# ProDoc_ChisFlash-MBCX-CQZ_2025-11-29.net
KiCad netlist of a schematic drawn in EasyEDA Pro
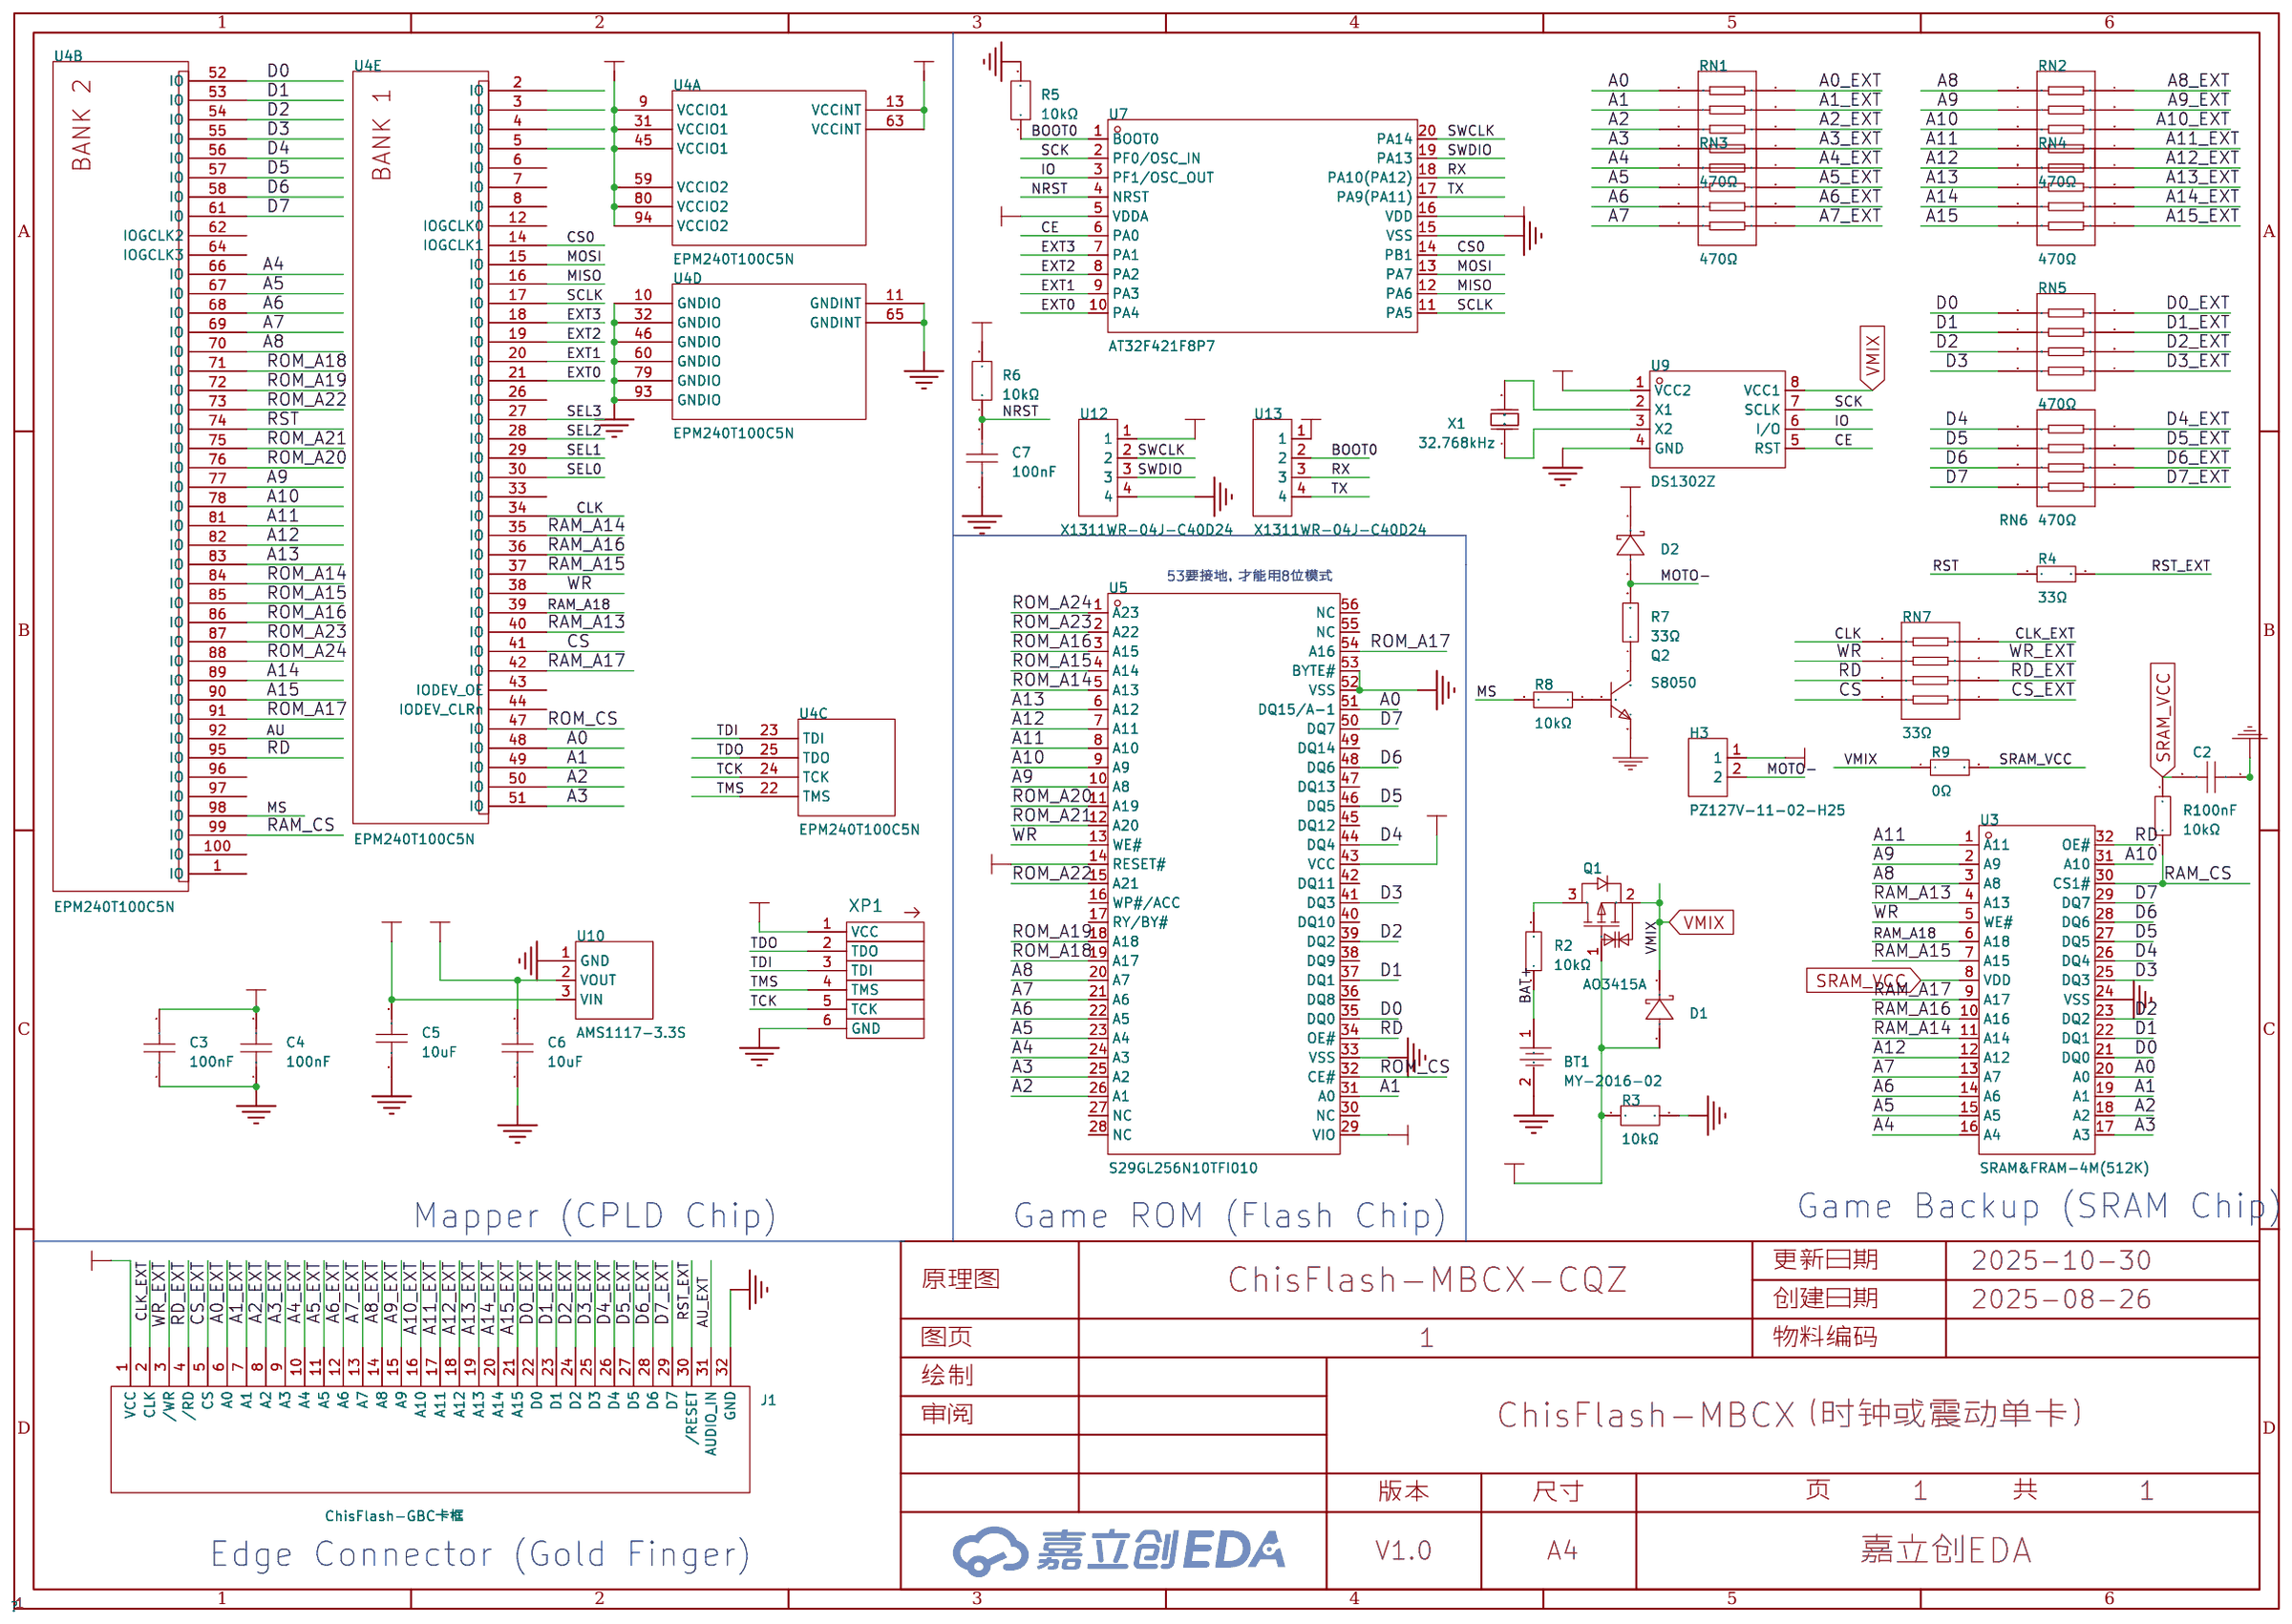
[diagram p0: schematic sheet]

(export (version "E")
  (design (tool "Eeschema 10.0.6"))
  (components
    (comp (ref "BT1")
      (value "MY-2016-02")
      (footprint "easyedapro:BAT-SMD_MY-2032-08")
      (description "连接器类型:电池扣;适用电池规格:CR2016;触头材质:磷青铜;触点电镀:镍;工作温度范围:-25°C~+85°C;")
      (fields (field (name "Manufacturer") "MYOUNG(美阳)"))
      (libsource (lib "easyedapro") (part "MY-2016-02"))
    )
    (comp (ref "C2")
      (value "100nF")
      (footprint "easyedapro:C0603")
      (description "容值:100nF;精度:±10%;额定电压:50V;材质(温度系数):X7R;")
      (fields
        (field (name "Manufacturer Part") "CGA0603X7R104K500JT")
        (field (name "Manufacturer") "HRE(芯声)")
      )
      (libsource (lib "easyedapro") (part "CGA0603X7R104K500JT"))
    )
    (comp (ref "C3")
      (value "100nF")
      (footprint "easyedapro:C0603")
      (description "容值:100nF;精度:±10%;额定电压:50V;材质(温度系数):X7R;")
      (fields
        (field (name "Manufacturer Part") "CGA0603X7R104K500JT")
        (field (name "Manufacturer") "HRE(芯声)")
      )
      (libsource (lib "easyedapro") (part "CGA0603X7R104K500JT"))
    )
    (comp (ref "C4")
      (value "100nF")
      (footprint "easyedapro:C0603")
      (description "容值:100nF;精度:±10%;额定电压:50V;材质(温度系数):X7R;")
      (fields
        (field (name "Manufacturer Part") "CGA0603X7R104K500JT")
        (field (name "Manufacturer") "HRE(芯声)")
      )
      (libsource (lib "easyedapro") (part "CGA0603X7R104K500JT"))
    )
    (comp (ref "C5")
      (value "10uF")
      (footprint "easyedapro:C0603")
      (description "容值:10uF;精度:±20%;额定电压:25V;材质(温度系数):X5R;")
      (fields
        (field (name "Manufacturer Part") "CL10A106MA8NRNC")
        (field (name "Manufacturer") "SAMSUNG(三星)")
      )
      (libsource (lib "easyedapro") (part "CL10A106MA8NRNC"))
    )
    (comp (ref "C6")
      (value "10uF")
      (footprint "easyedapro:C0603")
      (description "容值:10uF;精度:±20%;额定电压:25V;材质(温度系数):X5R;")
      (fields
        (field (name "Manufacturer Part") "CL10A106MA8NRNC")
        (field (name "Manufacturer") "SAMSUNG(三星)")
      )
      (libsource (lib "easyedapro") (part "CL10A106MA8NRNC"))
    )
    (comp (ref "C7")
      (value "100nF")
      (footprint "easyedapro:C0603")
      (description "容值:100nF;精度:±10%;额定电压:50V;材质(温度系数):X7R;")
      (fields
        (field (name "Manufacturer Part") "CGA0603X7R104K500JT")
        (field (name "Manufacturer") "HRE(芯声)")
      )
      (libsource (lib "easyedapro") (part "CGA0603X7R104K500JT"))
    )
    (comp (ref "D1")
      (value "RB751V-40")
      (footprint "easyedapro:SOD-323_L1.7-W1.3-LS2.6-RD-1")
      (description "二极管配置:独立式;正向压降(Vf):370mV@1mA;直流反向耐压(Vr):40V;平均整流电流(Io):30mA;")
      (fields (field (name "Manufacturer") "宏迦橙"))
      (libsource (lib "easyedapro") (part "RB751V-40_C7502691"))
    )
    (comp (ref "D2")
      (value "RB751V-40")
      (footprint "easyedapro:SOD-323_L1.7-W1.3-LS2.6-RD-1")
      (description "二极管配置:独立式;正向压降(Vf):370mV@1mA;直流反向耐压(Vr):40V;平均整流电流(Io):30mA;")
      (fields (field (name "Manufacturer") "宏迦橙"))
      (libsource (lib "easyedapro") (part "RB751V-40_C7502691"))
    )
    (comp (ref "H3")
      (value "PZ127V-11-02-H25")
      (footprint "easyedapro:HDR-TH_2P-P1.27-V-M-1")
      (fields (field (name "Manufacturer") "XFCN(兴飞)"))
      (libsource (lib "easyedapro") (part "PZ127V-11-02-H25"))
    )
    (comp (ref "J1")
      (value "ChisFlash-GBC卡框")
      (footprint "easyedapro:ChisFlash-GBC卡框")
      (libsource (lib "easyedapro") (part "ChisFlash-GBC卡框"))
    )
    (comp (ref "Q1")
      (value "AO3415A")
      (footprint "easyedapro:SOT-23-3_L3.0-W1.7-P0.95-LS2.9-BR")
      (fields (field (name "Manufacturer") "UMW(友台半导体)"))
      (libsource (lib "easyedapro") (part "AO3415A_C347479"))
    )
    (comp (ref "Q2")
      (value "S8050")
      (footprint "easyedapro:SOT-23-3_L2.9-W1.3-P1.90-LS2.3-BR")
      (description "晶体管类型:NPN;集电极电流(Ic):500mA;集射极击穿电压(Vceo):25V;耗散功率(Pd):300mW;直流电流增益(hFE):120@50mA,1.0V;")
      (fields (field (name "Manufacturer") "宏嘉诚"))
      (libsource (lib "easyedapro") (part "S8050_C20069125"))
    )
    (comp (ref "R1")
      (value "10kΩ")
      (footprint "easyedapro:R0603")
      (description "电阻类型:厚膜电阻;阻值:10kΩ;精度:±1%;功率:100mW;温度系数:±100ppm/°C;最大工作电压:75V;工作温度范围:-55°C~+155°C;")
      (fields
        (field (name "Manufacturer Part") "0603WAF1002T5E")
        (field (name "Manufacturer") "UNI-ROYAL(厚声)")
      )
      (libsource (lib "easyedapro") (part "0603WAF1002T5E"))
    )
    (comp (ref "R2")
      (value "10kΩ")
      (footprint "easyedapro:R0603")
      (description "电阻类型:厚膜电阻;阻值:10kΩ;精度:±1%;功率:100mW;温度系数:±100ppm/°C;最大工作电压:75V;工作温度范围:-55°C~+155°C;")
      (fields
        (field (name "Manufacturer Part") "0603WAF1002T5E")
        (field (name "Manufacturer") "UNI-ROYAL(厚声)")
      )
      (libsource (lib "easyedapro") (part "0603WAF1002T5E"))
    )
    (comp (ref "R3")
      (value "10kΩ")
      (footprint "easyedapro:R0603")
      (description "电阻类型:薄膜电阻;阻值:10kΩ;精度:±0.1%;功率:100mW;最大工作电压:75V;温度系数:±25ppm/°C;")
      (fields (field (name "Manufacturer Part") "RT0603BRD1010KL") (field (name "Manufacturer") "YAGEO(国巨)"))
      (libsource (lib "easyedapro") (part "RT0603BRD1010KL"))
    )
    (comp (ref "R4")
      (value "33Ω")
      (footprint "easyedapro:R0603")
      (description "电阻类型:厚膜电阻;阻值:33Ω;精度:±1%;功率:100mW;最大工作电压:75V;温度系数:±100ppm/°C;")
      (fields
        (field (name "Manufacturer Part") "0603WAF330JT5E")
        (field (name "Manufacturer") "UNI-ROYAL(厚声)")
      )
      (libsource (lib "easyedapro") (part "0603WAF330JT5E"))
    )
    (comp (ref "R5")
      (value "10kΩ")
      (footprint "easyedapro:R0603")
      (description "电阻类型:薄膜电阻;阻值:10kΩ;精度:±0.1%;功率:100mW;最大工作电压:75V;温度系数:±25ppm/°C;")
      (fields (field (name "Manufacturer Part") "RT0603BRD1010KL") (field (name "Manufacturer") "YAGEO(国巨)"))
      (libsource (lib "easyedapro") (part "RT0603BRD1010KL"))
    )
    (comp (ref "R6")
      (value "10kΩ")
      (footprint "easyedapro:R0603")
      (description "电阻类型:薄膜电阻;阻值:10kΩ;精度:±0.1%;功率:100mW;最大工作电压:75V;温度系数:±25ppm/°C;")
      (fields (field (name "Manufacturer Part") "RT0603BRD1010KL") (field (name "Manufacturer") "YAGEO(国巨)"))
      (libsource (lib "easyedapro") (part "RT0603BRD1010KL"))
    )
    (comp (ref "R7")
      (value "33Ω")
      (footprint "easyedapro:R0603")
      (description "电阻类型:厚膜电阻;阻值:33Ω;精度:±1%;功率:100mW;最大工作电压:75V;温度系数:±100ppm/°C;")
      (fields
        (field (name "Manufacturer Part") "0603WAF330JT5E")
        (field (name "Manufacturer") "UNI-ROYAL(厚声)")
      )
      (libsource (lib "easyedapro") (part "0603WAF330JT5E"))
    )
    (comp (ref "R8")
      (value "10kΩ")
      (footprint "easyedapro:R0603")
      (description "电阻类型:厚膜电阻;阻值:10kΩ;精度:±1%;功率:100mW;温度系数:±100ppm/°C;最大工作电压:75V;工作温度范围:-55°C~+155°C;")
      (fields
        (field (name "Manufacturer Part") "0603WAF1002T5E")
        (field (name "Manufacturer") "UNI-ROYAL(厚声)")
      )
      (libsource (lib "easyedapro") (part "0603WAF1002T5E"))
    )
    (comp (ref "R9")
      (value "0Ω")
      (footprint "easyedapro:R0603")
      (description "电阻类型:厚膜电阻;阻值:0Ω;精度:±1%;功率:100mW;工作电压:75V;温度系数:-;")
      (fields
        (field (name "Manufacturer Part") "0603WAF0000T5E")
        (field (name "Manufacturer") "UNI-ROYAL(厚声)")
      )
      (libsource (lib "easyedapro") (part "0603WAF0000T5E"))
    )
    (comp (ref "RN1")
      (value "470Ω")
      (footprint "easyedapro:RES-ARRAY-SMD_0603-8P-L3.2-W1.6-BL")
      (description "电阻器数:4;阻值:470Ω;精度:±5%;单个元件功率:62.5mW;温度系数:±200ppm/°C;")
      (fields
        (field (name "Manufacturer Part") "4D03WGJ0471T5E")
        (field (name "Manufacturer") "UNI-ROYAL(厚声)")
      )
      (libsource (lib "easyedapro") (part "4D03WGJ0471T5E"))
    )
    (comp (ref "RN2")
      (value "470Ω")
      (footprint "easyedapro:RES-ARRAY-SMD_0603-8P-L3.2-W1.6-BL")
      (description "电阻器数:4;阻值:470Ω;精度:±5%;单个元件功率:62.5mW;温度系数:±200ppm/°C;")
      (fields
        (field (name "Manufacturer Part") "4D03WGJ0471T5E")
        (field (name "Manufacturer") "UNI-ROYAL(厚声)")
      )
      (libsource (lib "easyedapro") (part "4D03WGJ0471T5E"))
    )
    (comp (ref "RN3")
      (value "470Ω")
      (footprint "easyedapro:RES-ARRAY-SMD_0603-8P-L3.2-W1.6-BL")
      (description "电阻器数:4;阻值:470Ω;精度:±5%;单个元件功率:62.5mW;温度系数:±200ppm/°C;")
      (fields
        (field (name "Manufacturer Part") "4D03WGJ0471T5E")
        (field (name "Manufacturer") "UNI-ROYAL(厚声)")
      )
      (libsource (lib "easyedapro") (part "4D03WGJ0471T5E"))
    )
    (comp (ref "RN4")
      (value "470Ω")
      (footprint "easyedapro:RES-ARRAY-SMD_0603-8P-L3.2-W1.6-BL")
      (description "电阻器数:4;阻值:470Ω;精度:±5%;单个元件功率:62.5mW;温度系数:±200ppm/°C;")
      (fields
        (field (name "Manufacturer Part") "4D03WGJ0471T5E")
        (field (name "Manufacturer") "UNI-ROYAL(厚声)")
      )
      (libsource (lib "easyedapro") (part "4D03WGJ0471T5E"))
    )
    (comp (ref "RN5")
      (value "470Ω")
      (footprint "easyedapro:RES-ARRAY-SMD_0603-8P-L3.2-W1.6-BL")
      (description "电阻器数:4;阻值:470Ω;精度:±5%;单个元件功率:62.5mW;温度系数:±200ppm/°C;")
      (fields
        (field (name "Manufacturer Part") "4D03WGJ0471T5E")
        (field (name "Manufacturer") "UNI-ROYAL(厚声)")
      )
      (libsource (lib "easyedapro") (part "4D03WGJ0471T5E"))
    )
    (comp (ref "RN6")
      (value "470Ω")
      (footprint "easyedapro:RES-ARRAY-SMD_0603-8P-L3.2-W1.6-BL")
      (description "电阻器数:4;阻值:470Ω;精度:±5%;单个元件功率:62.5mW;温度系数:±200ppm/°C;")
      (fields
        (field (name "Manufacturer Part") "4D03WGJ0471T5E")
        (field (name "Manufacturer") "UNI-ROYAL(厚声)")
      )
      (libsource (lib "easyedapro") (part "4D03WGJ0471T5E"))
    )
    (comp (ref "RN7")
      (value "33Ω")
      (footprint "easyedapro:RES-ARRAY-SMD_0603-8P-L3.2-W1.6-BL")
      (description "电阻器数:4;阻值:470Ω;精度:±5%;单个元件功率:62.5mW;温度系数:±200ppm/°C;")
      (fields
        (field (name "Manufacturer Part") "4D03WGF330JT5E")
        (field (name "Manufacturer") "UNI-ROYAL(厚声)")
      )
      (libsource (lib "easyedapro") (part "4D03WGJ0471T5E"))
    )
    (comp (ref "U3")
      (value "SRAM&FRAM-4M(512K)")
      (footprint "easyedapro:TSSOP-TSOP二合一_1")
      (libsource (lib "easyedapro") (part "SRAM&FRAM-4M(512K)"))
    )
    (comp (ref "U4")
      (value "EPM240T100C5N")
      (footprint "easyedapro:TQFP-100_L14.0-W14.0-P0.50-LS16.0-BL")
      (description "类型:其它PLD;逻辑门数量:-;逻辑单元数:-;逻辑阵列块数:240;")
      (fields (field (name "Manufacturer") "Intel/Altera"))
      (libsource (lib "easyedapro") (part "EPM240T100C5N"))
    )
    (comp (ref "U5")
      (value "S29GL256N10TFI010")
      (footprint "easyedapro:TSOP-56_L18.4-W14.0-P0.50-LS20.0-TL")
      (libsource (lib "easyedapro") (part "S29GL256N10TFI010"))
    )
    (comp (ref "U7")
      (value "AT32F421F8P7")
      (footprint "easyedapro:TSSOP-20_L6.5-W4.4-P0.65-LS6.4-BL")
      (fields (field (name "Manufacturer") "ARTERY(雅特力)"))
      (libsource (lib "easyedapro") (part "AT32F421F8P7"))
    )
    (comp (ref "U9")
      (value "DS1302Z")
      (footprint "easyedapro:SOP-8_L4.9-W3.9-P1.27-LS6.0-BL-1")
      (description "接口:三线串行接口;")
      (fields (field (name "Manufacturer") "JSMSEMI(杰盛微)"))
      (libsource (lib "easyedapro") (part "DS1302Z"))
    )
    (comp (ref "U10")
      (value "AMS1117-3.3S")
      (footprint "easyedapro:SOT-89-3_L4.5-W2.5-P1.50-LS4.2-BR")
      (description "输出类型:固定;工作电压:18V;输出电压:3.3V;输出电流:1A;电源纹波抑制比(PSRR):60dB@(120Hz);输出极性:正极;")
      (fields (field (name "Manufacturer") "UMW(友台半导体)"))
      (libsource (lib "easyedapro") (part "AMS1117-3.3_C347256"))
    )
    (comp (ref "U12")
      (value "X1311WR-04J-C40D24")
      (footprint "easyedapro:HDR-TH_4P-P1.27-H-M-W7.0-N_1")
      (fields (field (name "Manufacturer") "XKB Connection(中国星坤)"))
      (libsource (lib "easyedapro") (part "X1311WR-04J-C40D24"))
    )
    (comp (ref "U13")
      (value "X1311WR-04J-C40D24")
      (footprint "easyedapro:HDR-TH_4P-P1.27-H-M-W7.0-N_1")
      (fields (field (name "Manufacturer") "XKB Connection(中国星坤)"))
      (libsource (lib "easyedapro") (part "X1311WR-04J-C40D24"))
    )
    (comp (ref "X1")
      (value "32.768kHz")
      (footprint "easyedapro:CRYSTAL-SMD_2P-L2.0-W1.2")
      (description "晶振类型:贴片晶振;频率:32.768kHz;常温频差:±20ppm;负载电容:12.5pF;频率稳定度:±30ppm;")
      (fields
        (field (name "Manufacturer Part") "XKHEL89CGI-112YLC-32.768K")
        (field (name "Manufacturer") "YXC(扬兴晶振)")
      )
      (libsource (lib "easyedapro") (part "XKHEL89CGI-112YLC-32.768K"))
    )
    (comp (ref "XP1")
      (value "JTAG")
      (footprint "easyedapro:HDR-TH_6P-P1.27-V-M-1")
      (libsource (lib "easyedapro") (part "jtag"))
    )
  )
  (nets
    (net (code "1") (name "+3V3") (class "Default")
      (node (ref "C3") (pin "2") (pinfunction "2_2") (pintype "unspecified"))
      (node (ref "C4") (pin "2") (pinfunction "2_2") (pintype "unspecified"))
      (node (ref "C6") (pin "2") (pinfunction "2_2") (pintype "unspecified"))
      (node (ref "D1") (pin "2") (pinfunction "A_2") (pintype "unspecified"))
      (node (ref "D2") (pin "1") (pinfunction "K_1") (pintype "unspecified"))
      (node (ref "H3") (pin "1") (pinfunction "1_1") (pintype "unspecified"))
      (node (ref "Q1") (pin "1") (pinfunction "G_1") (pintype "unspecified"))
      (node (ref "R3") (pin "1") (pinfunction "1_1") (pintype "unspecified"))
      (node (ref "R6") (pin "2") (pinfunction "2_2") (pintype "unspecified"))
      (node (ref "U10") (pin "2") (pinfunction "VOUT_2") (pintype "unspecified"))
      (node (ref "U12") (pin "1") (pinfunction "1_1") (pintype "unspecified"))
      (node (ref "U13") (pin "1") (pinfunction "1_1") (pintype "unspecified"))
      (node (ref "U4") (pin "13") (pinfunction "VCCINT_13") (pintype "unspecified"))
      (node (ref "U4") (pin "31") (pinfunction "VCCIO1_31") (pintype "unspecified"))
      (node (ref "U4") (pin "45") (pinfunction "VCCIO1_45") (pintype "unspecified"))
      (node (ref "U4") (pin "59") (pinfunction "VCCIO2_59") (pintype "unspecified"))
      (node (ref "U4") (pin "63") (pinfunction "VCCINT_63") (pintype "unspecified"))
      (node (ref "U4") (pin "80") (pinfunction "VCCIO2_80") (pintype "unspecified"))
      (node (ref "U4") (pin "9") (pinfunction "VCCIO1_9") (pintype "unspecified"))
      (node (ref "U4") (pin "94") (pinfunction "VCCIO2_94") (pintype "unspecified"))
      (node (ref "U5") (pin "14") (pinfunction "RESET#_14") (pintype "unspecified"))
      (node (ref "U5") (pin "29") (pinfunction "VIO_29") (pintype "unspecified"))
      (node (ref "U5") (pin "43") (pinfunction "VCC_43") (pintype "unspecified"))
      (node (ref "U7") (pin "16") (pinfunction "VDD_16") (pintype "unspecified"))
      (node (ref "U7") (pin "5") (pinfunction "VDDA_5") (pintype "unspecified"))
      (node (ref "U9") (pin "1") (pinfunction "VCC2_1") (pintype "unspecified"))
      (node (ref "XP1") (pin "1") (pinfunction "VCC_1") (pintype "output"))
    )
    (net (code "2") (name "+5V") (class "Default")
      (node (ref "C5") (pin "2") (pinfunction "2_2") (pintype "unspecified"))
      (node (ref "J1") (pin "1") (pinfunction "VCC_1") (pintype "unspecified"))
      (node (ref "U10") (pin "3") (pinfunction "VIN_3") (pintype "unspecified"))
    )
    (net (code "3") (name "/A0") (class "Default")
      (node (ref "RN1") (pin "8") (pinfunction "8_8") (pintype "input"))
      (node (ref "U3") (pin "20") (pinfunction "A0_20") (pintype "unspecified"))
      (node (ref "U4") (pin "48") (pinfunction "IO_48") (pintype "bidirectional"))
      (node (ref "U5") (pin "51") (pinfunction "DQ15/A-1_51") (pintype "unspecified"))
    )
    (net (code "4") (name "/A0_EXT") (class "Default")
      (node (ref "J1") (pin "6") (pinfunction "A0_6") (pintype "unspecified"))
      (node (ref "RN1") (pin "1") (pinfunction "1_1") (pintype "input"))
    )
    (net (code "5") (name "/A1") (class "Default")
      (node (ref "RN1") (pin "7") (pinfunction "7_7") (pintype "input"))
      (node (ref "U3") (pin "19") (pinfunction "A1_19") (pintype "unspecified"))
      (node (ref "U4") (pin "49") (pinfunction "IO_49") (pintype "bidirectional"))
      (node (ref "U5") (pin "31") (pinfunction "A0_31") (pintype "unspecified"))
    )
    (net (code "6") (name "/A1_EXT") (class "Default")
      (node (ref "J1") (pin "7") (pinfunction "A1_7") (pintype "unspecified"))
      (node (ref "RN1") (pin "2") (pinfunction "2_2") (pintype "input"))
    )
    (net (code "7") (name "/A2") (class "Default")
      (node (ref "RN1") (pin "6") (pinfunction "6_6") (pintype "input"))
      (node (ref "U3") (pin "18") (pinfunction "A2_18") (pintype "unspecified"))
      (node (ref "U4") (pin "50") (pinfunction "IO_50") (pintype "bidirectional"))
      (node (ref "U5") (pin "26") (pinfunction "A1_26") (pintype "unspecified"))
    )
    (net (code "8") (name "/A2_EXT") (class "Default")
      (node (ref "J1") (pin "8") (pinfunction "A2_8") (pintype "unspecified"))
      (node (ref "RN1") (pin "3") (pinfunction "3_3") (pintype "input"))
    )
    (net (code "9") (name "/A3") (class "Default")
      (node (ref "RN1") (pin "5") (pinfunction "5_5") (pintype "input"))
      (node (ref "U3") (pin "17") (pinfunction "A3_17") (pintype "unspecified"))
      (node (ref "U4") (pin "51") (pinfunction "IO_51") (pintype "bidirectional"))
      (node (ref "U5") (pin "25") (pinfunction "A2_25") (pintype "unspecified"))
    )
    (net (code "10") (name "/A3_EXT") (class "Default")
      (node (ref "J1") (pin "9") (pinfunction "A3_9") (pintype "unspecified"))
      (node (ref "RN1") (pin "4") (pinfunction "4_4") (pintype "input"))
    )
    (net (code "11") (name "/A4") (class "Default")
      (node (ref "RN3") (pin "8") (pinfunction "8_8") (pintype "input"))
      (node (ref "U3") (pin "16") (pinfunction "A4_16") (pintype "unspecified"))
      (node (ref "U4") (pin "66") (pinfunction "IO_66") (pintype "bidirectional"))
      (node (ref "U5") (pin "24") (pinfunction "A3_24") (pintype "unspecified"))
    )
    (net (code "12") (name "/A4_EXT") (class "Default")
      (node (ref "J1") (pin "10") (pinfunction "A4_10") (pintype "unspecified"))
      (node (ref "RN3") (pin "1") (pinfunction "1_1") (pintype "input"))
    )
    (net (code "13") (name "/A5") (class "Default")
      (node (ref "RN3") (pin "7") (pinfunction "7_7") (pintype "input"))
      (node (ref "U3") (pin "15") (pinfunction "A5_15") (pintype "unspecified"))
      (node (ref "U4") (pin "67") (pinfunction "IO_67") (pintype "bidirectional"))
      (node (ref "U5") (pin "23") (pinfunction "A4_23") (pintype "unspecified"))
    )
    (net (code "14") (name "/A5_EXT") (class "Default")
      (node (ref "J1") (pin "11") (pinfunction "A5_11") (pintype "unspecified"))
      (node (ref "RN3") (pin "2") (pinfunction "2_2") (pintype "input"))
    )
    (net (code "15") (name "/A6") (class "Default")
      (node (ref "RN3") (pin "6") (pinfunction "6_6") (pintype "input"))
      (node (ref "U3") (pin "14") (pinfunction "A6_14") (pintype "unspecified"))
      (node (ref "U4") (pin "68") (pinfunction "IO_68") (pintype "bidirectional"))
      (node (ref "U5") (pin "22") (pinfunction "A5_22") (pintype "unspecified"))
    )
    (net (code "16") (name "/A6_EXT") (class "Default")
      (node (ref "J1") (pin "12") (pinfunction "A6_12") (pintype "unspecified"))
      (node (ref "RN3") (pin "3") (pinfunction "3_3") (pintype "input"))
    )
    (net (code "17") (name "/A7") (class "Default")
      (node (ref "RN3") (pin "5") (pinfunction "5_5") (pintype "input"))
      (node (ref "U3") (pin "13") (pinfunction "A7_13") (pintype "unspecified"))
      (node (ref "U4") (pin "69") (pinfunction "IO_69") (pintype "bidirectional"))
      (node (ref "U5") (pin "21") (pinfunction "A6_21") (pintype "unspecified"))
    )
    (net (code "18") (name "/A7_EXT") (class "Default")
      (node (ref "J1") (pin "13") (pinfunction "A7_13") (pintype "unspecified"))
      (node (ref "RN3") (pin "4") (pinfunction "4_4") (pintype "input"))
    )
    (net (code "19") (name "/A8") (class "Default")
      (node (ref "RN2") (pin "8") (pinfunction "8_8") (pintype "input"))
      (node (ref "U3") (pin "3") (pinfunction "A8_3") (pintype "unspecified"))
      (node (ref "U4") (pin "70") (pinfunction "IO_70") (pintype "bidirectional"))
      (node (ref "U5") (pin "20") (pinfunction "A7_20") (pintype "unspecified"))
    )
    (net (code "20") (name "/A8_EXT") (class "Default")
      (node (ref "J1") (pin "14") (pinfunction "A8_14") (pintype "unspecified"))
      (node (ref "RN2") (pin "1") (pinfunction "1_1") (pintype "input"))
    )
    (net (code "21") (name "/A9") (class "Default")
      (node (ref "RN2") (pin "7") (pinfunction "7_7") (pintype "input"))
      (node (ref "U3") (pin "2") (pinfunction "A9_2") (pintype "unspecified"))
      (node (ref "U4") (pin "77") (pinfunction "IO_77") (pintype "bidirectional"))
      (node (ref "U5") (pin "10") (pinfunction "A8_10") (pintype "unspecified"))
    )
    (net (code "22") (name "/A9_EXT") (class "Default")
      (node (ref "J1") (pin "15") (pinfunction "A9_15") (pintype "unspecified"))
      (node (ref "RN2") (pin "2") (pinfunction "2_2") (pintype "input"))
    )
    (net (code "23") (name "/A10") (class "Default")
      (node (ref "RN2") (pin "6") (pinfunction "6_6") (pintype "input"))
      (node (ref "U3") (pin "31") (pinfunction "A10_31") (pintype "unspecified"))
      (node (ref "U4") (pin "78") (pinfunction "IO_78") (pintype "bidirectional"))
      (node (ref "U5") (pin "9") (pinfunction "A9_9") (pintype "unspecified"))
    )
    (net (code "24") (name "/A10_EXT") (class "Default")
      (node (ref "J1") (pin "16") (pinfunction "A10_16") (pintype "unspecified"))
      (node (ref "RN2") (pin "3") (pinfunction "3_3") (pintype "input"))
    )
    (net (code "25") (name "/A11") (class "Default")
      (node (ref "RN2") (pin "5") (pinfunction "5_5") (pintype "input"))
      (node (ref "U3") (pin "1") (pinfunction "A11_1") (pintype "unspecified"))
      (node (ref "U4") (pin "81") (pinfunction "IO_81") (pintype "bidirectional"))
      (node (ref "U5") (pin "8") (pinfunction "A10_8") (pintype "unspecified"))
    )
    (net (code "26") (name "/A11_EXT") (class "Default")
      (node (ref "J1") (pin "17") (pinfunction "A11_17") (pintype "unspecified"))
      (node (ref "RN2") (pin "4") (pinfunction "4_4") (pintype "input"))
    )
    (net (code "27") (name "/A12") (class "Default")
      (node (ref "RN4") (pin "8") (pinfunction "8_8") (pintype "input"))
      (node (ref "U3") (pin "12") (pinfunction "A12_12") (pintype "unspecified"))
      (node (ref "U4") (pin "82") (pinfunction "IO_82") (pintype "bidirectional"))
      (node (ref "U5") (pin "7") (pinfunction "A11_7") (pintype "unspecified"))
    )
    (net (code "28") (name "/A12_EXT") (class "Default")
      (node (ref "J1") (pin "18") (pinfunction "A12_18") (pintype "unspecified"))
      (node (ref "RN4") (pin "1") (pinfunction "1_1") (pintype "input"))
    )
    (net (code "29") (name "/A13") (class "Default")
      (node (ref "RN4") (pin "7") (pinfunction "7_7") (pintype "input"))
      (node (ref "U4") (pin "83") (pinfunction "IO_83") (pintype "bidirectional"))
      (node (ref "U5") (pin "6") (pinfunction "A12_6") (pintype "unspecified"))
    )
    (net (code "30") (name "/A13_EXT") (class "Default")
      (node (ref "J1") (pin "19") (pinfunction "A13_19") (pintype "unspecified"))
      (node (ref "RN4") (pin "2") (pinfunction "2_2") (pintype "input"))
    )
    (net (code "31") (name "/A14") (class "Default")
      (node (ref "RN4") (pin "6") (pinfunction "6_6") (pintype "input"))
      (node (ref "U4") (pin "89") (pinfunction "IO_89") (pintype "bidirectional"))
    )
    (net (code "32") (name "/A14_EXT") (class "Default")
      (node (ref "J1") (pin "20") (pinfunction "A14_20") (pintype "unspecified"))
      (node (ref "RN4") (pin "3") (pinfunction "3_3") (pintype "input"))
    )
    (net (code "33") (name "/A15") (class "Default")
      (node (ref "RN4") (pin "5") (pinfunction "5_5") (pintype "input"))
      (node (ref "U4") (pin "90") (pinfunction "IO_90") (pintype "bidirectional"))
    )
    (net (code "34") (name "/A15_EXT") (class "Default")
      (node (ref "J1") (pin "21") (pinfunction "A15_21") (pintype "unspecified"))
      (node (ref "RN4") (pin "4") (pinfunction "4_4") (pintype "input"))
    )
    (net (code "35") (name "/AU") (class "Default")
      (node (ref "U4") (pin "92") (pinfunction "IO_92") (pintype "bidirectional"))
    )
    (net (code "36") (name "/AU_EXT") (class "Default")
      (node (ref "J1") (pin "31") (pinfunction "AUDIO_IN_31") (pintype "unspecified"))
    )
    (net (code "37") (name "/BAT+") (class "Default")
      (node (ref "BT1") (pin "1") (pinfunction "1_1") (pintype "input"))
      (node (ref "R2") (pin "1") (pinfunction "1_1") (pintype "input"))
    )
    (net (code "38") (name "/BOOT0") (class "Default")
      (node (ref "R5") (pin "1") (pinfunction "1_1") (pintype "unspecified"))
      (node (ref "U13") (pin "2") (pinfunction "2_2") (pintype "unspecified"))
      (node (ref "U7") (pin "1") (pinfunction "BOOT0_1") (pintype "unspecified"))
    )
    (net (code "39") (name "/CE") (class "Default")
      (node (ref "U7") (pin "6") (pinfunction "PA0_6") (pintype "unspecified"))
      (node (ref "U9") (pin "5") (pinfunction "RST_5") (pintype "unspecified"))
    )
    (net (code "40") (name "/CLK") (class "Default")
      (node (ref "RN7") (pin "8") (pinfunction "8_8") (pintype "input"))
      (node (ref "U4") (pin "34") (pinfunction "IO_34") (pintype "bidirectional"))
    )
    (net (code "41") (name "/CLK_EXT") (class "Default")
      (node (ref "J1") (pin "2") (pinfunction "CLK_2") (pintype "unspecified"))
      (node (ref "RN7") (pin "1") (pinfunction "1_1") (pintype "input"))
    )
    (net (code "42") (name "/CS") (class "Default")
      (node (ref "RN7") (pin "5") (pinfunction "5_5") (pintype "input"))
      (node (ref "U4") (pin "41") (pinfunction "IO_41") (pintype "bidirectional"))
    )
    (net (code "43") (name "/CS0") (class "Default")
      (node (ref "U4") (pin "14") (pinfunction "IOGCLK1_14") (pintype "bidirectional"))
      (node (ref "U7") (pin "14") (pinfunction "PB1_14") (pintype "unspecified"))
    )
    (net (code "44") (name "/CS_EXT") (class "Default")
      (node (ref "J1") (pin "5") (pinfunction "CS_5") (pintype "unspecified"))
      (node (ref "RN7") (pin "4") (pinfunction "4_4") (pintype "input"))
    )
    (net (code "45") (name "/D0") (class "Default")
      (node (ref "RN5") (pin "8") (pinfunction "8_8") (pintype "input"))
      (node (ref "U3") (pin "21") (pinfunction "DQ0_21") (pintype "unspecified"))
      (node (ref "U4") (pin "52") (pinfunction "IO_52") (pintype "bidirectional"))
      (node (ref "U5") (pin "35") (pinfunction "DQ0_35") (pintype "unspecified"))
    )
    (net (code "46") (name "/D0_EXT") (class "Default")
      (node (ref "J1") (pin "22") (pinfunction "D0_22") (pintype "unspecified"))
      (node (ref "RN5") (pin "1") (pinfunction "1_1") (pintype "input"))
    )
    (net (code "47") (name "/D1") (class "Default")
      (node (ref "RN5") (pin "7") (pinfunction "7_7") (pintype "input"))
      (node (ref "U3") (pin "22") (pinfunction "DQ1_22") (pintype "unspecified"))
      (node (ref "U4") (pin "53") (pinfunction "IO_53") (pintype "bidirectional"))
      (node (ref "U5") (pin "37") (pinfunction "DQ1_37") (pintype "unspecified"))
    )
    (net (code "48") (name "/D1_EXT") (class "Default")
      (node (ref "J1") (pin "23") (pinfunction "D1_23") (pintype "unspecified"))
      (node (ref "RN5") (pin "2") (pinfunction "2_2") (pintype "input"))
    )
    (net (code "49") (name "/D2") (class "Default")
      (node (ref "RN5") (pin "6") (pinfunction "6_6") (pintype "input"))
      (node (ref "U3") (pin "23") (pinfunction "DQ2_23") (pintype "unspecified"))
      (node (ref "U4") (pin "54") (pinfunction "IO_54") (pintype "bidirectional"))
      (node (ref "U5") (pin "39") (pinfunction "DQ2_39") (pintype "unspecified"))
    )
    (net (code "50") (name "/D2_EXT") (class "Default")
      (node (ref "J1") (pin "24") (pinfunction "D2_24") (pintype "unspecified"))
      (node (ref "RN5") (pin "3") (pinfunction "3_3") (pintype "input"))
    )
    (net (code "51") (name "/D3") (class "Default")
      (node (ref "RN5") (pin "5") (pinfunction "5_5") (pintype "input"))
      (node (ref "U3") (pin "25") (pinfunction "DQ3_25") (pintype "unspecified"))
      (node (ref "U4") (pin "55") (pinfunction "IO_55") (pintype "bidirectional"))
      (node (ref "U5") (pin "41") (pinfunction "DQ3_41") (pintype "unspecified"))
    )
    (net (code "52") (name "/D3_EXT") (class "Default")
      (node (ref "J1") (pin "25") (pinfunction "D3_25") (pintype "unspecified"))
      (node (ref "RN5") (pin "4") (pinfunction "4_4") (pintype "input"))
    )
    (net (code "53") (name "/D4") (class "Default")
      (node (ref "RN6") (pin "8") (pinfunction "8_8") (pintype "input"))
      (node (ref "U3") (pin "26") (pinfunction "DQ4_26") (pintype "unspecified"))
      (node (ref "U4") (pin "56") (pinfunction "IO_56") (pintype "bidirectional"))
      (node (ref "U5") (pin "44") (pinfunction "DQ4_44") (pintype "unspecified"))
    )
    (net (code "54") (name "/D4_EXT") (class "Default")
      (node (ref "J1") (pin "26") (pinfunction "D4_26") (pintype "unspecified"))
      (node (ref "RN6") (pin "1") (pinfunction "1_1") (pintype "input"))
    )
    (net (code "55") (name "/D5") (class "Default")
      (node (ref "RN6") (pin "7") (pinfunction "7_7") (pintype "input"))
      (node (ref "U3") (pin "27") (pinfunction "DQ5_27") (pintype "unspecified"))
      (node (ref "U4") (pin "57") (pinfunction "IO_57") (pintype "bidirectional"))
      (node (ref "U5") (pin "46") (pinfunction "DQ5_46") (pintype "unspecified"))
    )
    (net (code "56") (name "/D5_EXT") (class "Default")
      (node (ref "J1") (pin "27") (pinfunction "D5_27") (pintype "unspecified"))
      (node (ref "RN6") (pin "2") (pinfunction "2_2") (pintype "input"))
    )
    (net (code "57") (name "/D6") (class "Default")
      (node (ref "RN6") (pin "6") (pinfunction "6_6") (pintype "input"))
      (node (ref "U3") (pin "28") (pinfunction "DQ6_28") (pintype "unspecified"))
      (node (ref "U4") (pin "58") (pinfunction "IO_58") (pintype "bidirectional"))
      (node (ref "U5") (pin "48") (pinfunction "DQ6_48") (pintype "unspecified"))
    )
    (net (code "58") (name "/D6_EXT") (class "Default")
      (node (ref "J1") (pin "28") (pinfunction "D6_28") (pintype "unspecified"))
      (node (ref "RN6") (pin "3") (pinfunction "3_3") (pintype "input"))
    )
    (net (code "59") (name "/D7") (class "Default")
      (node (ref "RN6") (pin "5") (pinfunction "5_5") (pintype "input"))
      (node (ref "U3") (pin "29") (pinfunction "DQ7_29") (pintype "unspecified"))
      (node (ref "U4") (pin "61") (pinfunction "IO_61") (pintype "bidirectional"))
      (node (ref "U5") (pin "50") (pinfunction "DQ7_50") (pintype "unspecified"))
    )
    (net (code "60") (name "/D7_EXT") (class "Default")
      (node (ref "J1") (pin "29") (pinfunction "D7_29") (pintype "unspecified"))
      (node (ref "RN6") (pin "4") (pinfunction "4_4") (pintype "input"))
    )
    (net (code "61") (name "/EXT0") (class "Default")
      (node (ref "U4") (pin "21") (pinfunction "IO_21") (pintype "bidirectional"))
      (node (ref "U7") (pin "10") (pinfunction "PA4_10") (pintype "unspecified"))
    )
    (net (code "62") (name "/EXT1") (class "Default")
      (node (ref "U4") (pin "20") (pinfunction "IO_20") (pintype "bidirectional"))
      (node (ref "U7") (pin "9") (pinfunction "PA3_9") (pintype "unspecified"))
    )
    (net (code "63") (name "/EXT2") (class "Default")
      (node (ref "U4") (pin "19") (pinfunction "IO_19") (pintype "bidirectional"))
      (node (ref "U7") (pin "8") (pinfunction "PA2_8") (pintype "unspecified"))
    )
    (net (code "64") (name "/EXT3") (class "Default")
      (node (ref "U4") (pin "18") (pinfunction "IO_18") (pintype "bidirectional"))
      (node (ref "U7") (pin "7") (pinfunction "PA1_7") (pintype "unspecified"))
    )
    (net (code "65") (name "/IO") (class "Default")
      (node (ref "U7") (pin "3") (pinfunction "PF1/OSC_OUT_3") (pintype "unspecified"))
      (node (ref "U9") (pin "6") (pinfunction "I/O_6") (pintype "unspecified"))
    )
    (net (code "66") (name "/MISO") (class "Default")
      (node (ref "U4") (pin "16") (pinfunction "IO_16") (pintype "bidirectional"))
      (node (ref "U7") (pin "12") (pinfunction "PA6_12") (pintype "unspecified"))
    )
    (net (code "67") (name "/MOSI") (class "Default")
      (node (ref "U4") (pin "15") (pinfunction "IO_15") (pintype "bidirectional"))
      (node (ref "U7") (pin "13") (pinfunction "PA7_13") (pintype "unspecified"))
    )
    (net (code "68") (name "/MOTO-") (class "Default")
      (node (ref "D2") (pin "2") (pinfunction "A_2") (pintype "unspecified"))
      (node (ref "H3") (pin "2") (pinfunction "2_2") (pintype "unspecified"))
      (node (ref "R7") (pin "2") (pinfunction "2_2") (pintype "input"))
    )
    (net (code "69") (name "/MS") (class "Default")
      (node (ref "R8") (pin "2") (pinfunction "2_2") (pintype "input"))
      (node (ref "U4") (pin "98") (pinfunction "IO_98") (pintype "bidirectional"))
    )
    (net (code "70") (name "/NRST") (class "Default")
      (node (ref "C7") (pin "1") (pinfunction "1_1") (pintype "unspecified"))
      (node (ref "R6") (pin "1") (pinfunction "1_1") (pintype "unspecified"))
      (node (ref "U7") (pin "4") (pinfunction "NRST_4") (pintype "unspecified"))
    )
    (net (code "71") (name "/RAM_A13") (class "Default")
      (node (ref "U3") (pin "4") (pinfunction "A13_4") (pintype "unspecified"))
      (node (ref "U4") (pin "40") (pinfunction "IO_40") (pintype "bidirectional"))
    )
    (net (code "72") (name "/RAM_A14") (class "Default")
      (node (ref "U3") (pin "11") (pinfunction "A14_11") (pintype "unspecified"))
      (node (ref "U4") (pin "35") (pinfunction "IO_35") (pintype "bidirectional"))
    )
    (net (code "73") (name "/RAM_A15") (class "Default")
      (node (ref "U3") (pin "7") (pinfunction "A15_7") (pintype "unspecified"))
      (node (ref "U4") (pin "37") (pinfunction "IO_37") (pintype "bidirectional"))
    )
    (net (code "74") (name "/RAM_A16") (class "Default")
      (node (ref "U3") (pin "10") (pinfunction "A16_10") (pintype "unspecified"))
      (node (ref "U4") (pin "36") (pinfunction "IO_36") (pintype "bidirectional"))
    )
    (net (code "75") (name "/RAM_A17") (class "Default")
      (node (ref "U3") (pin "9") (pinfunction "A17_9") (pintype "unspecified"))
      (node (ref "U4") (pin "42") (pinfunction "IO_42") (pintype "bidirectional"))
    )
    (net (code "76") (name "/RAM_A18") (class "Default")
      (node (ref "U3") (pin "6") (pinfunction "A18_6") (pintype "unspecified"))
      (node (ref "U4") (pin "39") (pinfunction "IO_39") (pintype "bidirectional"))
    )
    (net (code "77") (name "/RAM_CS") (class "Default")
      (node (ref "R1") (pin "1") (pinfunction "1_1") (pintype "input"))
      (node (ref "U3") (pin "30") (pinfunction "CS1#_30") (pintype "unspecified"))
      (node (ref "U4") (pin "99") (pinfunction "IO_99") (pintype "bidirectional"))
    )
    (net (code "78") (name "/RD") (class "Default")
      (node (ref "RN7") (pin "6") (pinfunction "6_6") (pintype "input"))
      (node (ref "U3") (pin "32") (pinfunction "OE#_32") (pintype "unspecified"))
      (node (ref "U4") (pin "95") (pinfunction "IO_95") (pintype "bidirectional"))
      (node (ref "U5") (pin "34") (pinfunction "OE#_34") (pintype "unspecified"))
    )
    (net (code "79") (name "/RD_EXT") (class "Default")
      (node (ref "J1") (pin "4") (pinfunction "/RD_4") (pintype "unspecified"))
      (node (ref "RN7") (pin "3") (pinfunction "3_3") (pintype "input"))
    )
    (net (code "80") (name "/ROM_A14") (class "Default")
      (node (ref "U4") (pin "84") (pinfunction "IO_84") (pintype "bidirectional"))
      (node (ref "U5") (pin "5") (pinfunction "A13_5") (pintype "unspecified"))
    )
    (net (code "81") (name "/ROM_A15") (class "Default")
      (node (ref "U4") (pin "85") (pinfunction "IO_85") (pintype "bidirectional"))
      (node (ref "U5") (pin "4") (pinfunction "A14_4") (pintype "unspecified"))
    )
    (net (code "82") (name "/ROM_A16") (class "Default")
      (node (ref "U4") (pin "86") (pinfunction "IO_86") (pintype "bidirectional"))
      (node (ref "U5") (pin "3") (pinfunction "A15_3") (pintype "unspecified"))
    )
    (net (code "83") (name "/ROM_A17") (class "Default")
      (node (ref "U4") (pin "91") (pinfunction "IO_91") (pintype "bidirectional"))
      (node (ref "U5") (pin "54") (pinfunction "A16_54") (pintype "unspecified"))
    )
    (net (code "84") (name "/ROM_A18") (class "Default")
      (node (ref "U4") (pin "71") (pinfunction "IO_71") (pintype "bidirectional"))
      (node (ref "U5") (pin "19") (pinfunction "A17_19") (pintype "unspecified"))
    )
    (net (code "85") (name "/ROM_A19") (class "Default")
      (node (ref "U4") (pin "72") (pinfunction "IO_72") (pintype "bidirectional"))
      (node (ref "U5") (pin "18") (pinfunction "A18_18") (pintype "unspecified"))
    )
    (net (code "86") (name "/ROM_A20") (class "Default")
      (node (ref "U4") (pin "76") (pinfunction "IO_76") (pintype "bidirectional"))
      (node (ref "U5") (pin "11") (pinfunction "A19_11") (pintype "unspecified"))
    )
    (net (code "87") (name "/ROM_A21") (class "Default")
      (node (ref "U4") (pin "75") (pinfunction "IO_75") (pintype "bidirectional"))
      (node (ref "U5") (pin "12") (pinfunction "A20_12") (pintype "unspecified"))
    )
    (net (code "88") (name "/ROM_A22") (class "Default")
      (node (ref "U4") (pin "73") (pinfunction "IO_73") (pintype "bidirectional"))
      (node (ref "U5") (pin "15") (pinfunction "A21_15") (pintype "unspecified"))
    )
    (net (code "89") (name "/ROM_A23") (class "Default")
      (node (ref "U4") (pin "87") (pinfunction "IO_87") (pintype "bidirectional"))
      (node (ref "U5") (pin "2") (pinfunction "A22_2") (pintype "unspecified"))
    )
    (net (code "90") (name "/ROM_A24") (class "Default")
      (node (ref "U4") (pin "88") (pinfunction "IO_88") (pintype "bidirectional"))
      (node (ref "U5") (pin "1") (pinfunction "A23_1") (pintype "unspecified"))
    )
    (net (code "91") (name "/ROM_CS") (class "Default")
      (node (ref "U4") (pin "47") (pinfunction "IO_47") (pintype "bidirectional"))
      (node (ref "U5") (pin "32") (pinfunction "CE#_32") (pintype "unspecified"))
    )
    (net (code "92") (name "/RST") (class "Default")
      (node (ref "R4") (pin "1") (pinfunction "1_1") (pintype "input"))
      (node (ref "U4") (pin "74") (pinfunction "IO_74") (pintype "bidirectional"))
    )
    (net (code "93") (name "/RST_EXT") (class "Default")
      (node (ref "J1") (pin "30") (pinfunction "/RESET_30") (pintype "unspecified"))
      (node (ref "R4") (pin "2") (pinfunction "2_2") (pintype "input"))
    )
    (net (code "94") (name "/RX") (class "Default")
      (node (ref "U13") (pin "3") (pinfunction "3_3") (pintype "unspecified"))
      (node (ref "U7") (pin "18") (pinfunction "PA10(PA12)_18") (pintype "unspecified"))
    )
    (net (code "95") (name "/SCK") (class "Default")
      (node (ref "U7") (pin "2") (pinfunction "PF0/OSC_IN_2") (pintype "unspecified"))
      (node (ref "U9") (pin "7") (pinfunction "SCLK_7") (pintype "unspecified"))
    )
    (net (code "96") (name "/SCLK") (class "Default")
      (node (ref "U4") (pin "17") (pinfunction "IO_17") (pintype "bidirectional"))
      (node (ref "U7") (pin "11") (pinfunction "PA5_11") (pintype "unspecified"))
    )
    (net (code "97") (name "/SEL0") (class "Default")
      (node (ref "U4") (pin "30") (pinfunction "IO_30") (pintype "bidirectional"))
    )
    (net (code "98") (name "/SEL1") (class "Default")
      (node (ref "U4") (pin "29") (pinfunction "IO_29") (pintype "bidirectional"))
    )
    (net (code "99") (name "/SEL2") (class "Default")
      (node (ref "U4") (pin "28") (pinfunction "IO_28") (pintype "bidirectional"))
    )
    (net (code "100") (name "/SEL3") (class "Default")
      (node (ref "U4") (pin "27") (pinfunction "IO_27") (pintype "bidirectional"))
    )
    (net (code "101") (name "/SWCLK") (class "Default")
      (node (ref "U12") (pin "2") (pinfunction "2_2") (pintype "unspecified"))
      (node (ref "U7") (pin "20") (pinfunction "PA14_20") (pintype "unspecified"))
    )
    (net (code "102") (name "/SWDIO") (class "Default")
      (node (ref "U12") (pin "3") (pinfunction "3_3") (pintype "unspecified"))
      (node (ref "U7") (pin "19") (pinfunction "PA13_19") (pintype "unspecified"))
    )
    (net (code "103") (name "/TCK") (class "Default")
      (node (ref "U4") (pin "24") (pinfunction "TCK_24") (pintype "unspecified"))
      (node (ref "XP1") (pin "5") (pinfunction "TCK_5") (pintype "input"))
    )
    (net (code "104") (name "/TDI") (class "Default")
      (node (ref "U4") (pin "23") (pinfunction "TDI_23") (pintype "unspecified"))
      (node (ref "XP1") (pin "3") (pinfunction "TDI_3") (pintype "output"))
    )
    (net (code "105") (name "/TDO") (class "Default")
      (node (ref "U4") (pin "25") (pinfunction "TDO_25") (pintype "output"))
      (node (ref "XP1") (pin "2") (pinfunction "TDO_2") (pintype "output"))
    )
    (net (code "106") (name "/TMS") (class "Default")
      (node (ref "U4") (pin "22") (pinfunction "TMS_22") (pintype "unspecified"))
      (node (ref "XP1") (pin "4") (pinfunction "TMS_4") (pintype "output"))
    )
    (net (code "107") (name "/TX") (class "Default")
      (node (ref "U13") (pin "4") (pinfunction "4_4") (pintype "unspecified"))
      (node (ref "U7") (pin "17") (pinfunction "PA9(PA11)_17") (pintype "unspecified"))
    )
    (net (code "108") (name "/WR") (class "Default")
      (node (ref "RN7") (pin "7") (pinfunction "7_7") (pintype "input"))
      (node (ref "U3") (pin "5") (pinfunction "WE#_5") (pintype "unspecified"))
      (node (ref "U4") (pin "38") (pinfunction "IO_38") (pintype "bidirectional"))
      (node (ref "U5") (pin "13") (pinfunction "WE#_13") (pintype "unspecified"))
    )
    (net (code "109") (name "/WR_EXT") (class "Default")
      (node (ref "J1") (pin "3") (pinfunction "/WR_3") (pintype "unspecified"))
      (node (ref "RN7") (pin "2") (pinfunction "2_2") (pintype "input"))
    )
    (net (code "110") (name "GND") (class "Default")
      (node (ref "BT1") (pin "2") (pinfunction "2_2") (pintype "input"))
      (node (ref "C2") (pin "1") (pinfunction "1_1") (pintype "unspecified"))
      (node (ref "C3") (pin "1") (pinfunction "1_1") (pintype "unspecified"))
      (node (ref "C4") (pin "1") (pinfunction "1_1") (pintype "unspecified"))
      (node (ref "C5") (pin "1") (pinfunction "1_1") (pintype "unspecified"))
      (node (ref "C6") (pin "1") (pinfunction "1_1") (pintype "unspecified"))
      (node (ref "C7") (pin "2") (pinfunction "2_2") (pintype "unspecified"))
      (node (ref "J1") (pin "32") (pinfunction "GND_32") (pintype "unspecified"))
      (node (ref "Q2") (pin "2") (pinfunction "E_2") (pintype "input"))
      (node (ref "R3") (pin "2") (pinfunction "2_2") (pintype "unspecified"))
      (node (ref "R5") (pin "2") (pinfunction "2_2") (pintype "unspecified"))
      (node (ref "U10") (pin "1") (pinfunction "GND_1") (pintype "unspecified"))
      (node (ref "U12") (pin "4") (pinfunction "4_4") (pintype "unspecified"))
      (node (ref "U3") (pin "24") (pinfunction "VSS_24") (pintype "unspecified"))
      (node (ref "U4") (pin "10") (pinfunction "GNDIO_10") (pintype "unspecified"))
      (node (ref "U4") (pin "11") (pinfunction "GNDINT_11") (pintype "unspecified"))
      (node (ref "U4") (pin "32") (pinfunction "GNDIO_32") (pintype "unspecified"))
      (node (ref "U4") (pin "46") (pinfunction "GNDIO_46") (pintype "unspecified"))
      (node (ref "U4") (pin "60") (pinfunction "GNDIO_60") (pintype "unspecified"))
      (node (ref "U4") (pin "65") (pinfunction "GNDINT_65") (pintype "unspecified"))
      (node (ref "U4") (pin "79") (pinfunction "GNDIO_79") (pintype "unspecified"))
      (node (ref "U4") (pin "93") (pinfunction "GNDIO_93") (pintype "unspecified"))
      (node (ref "U5") (pin "33") (pinfunction "VSS_33") (pintype "unspecified"))
      (node (ref "U5") (pin "52") (pinfunction "VSS_52") (pintype "unspecified"))
      (node (ref "U5") (pin "53") (pinfunction "BYTE#_53") (pintype "unspecified"))
      (node (ref "U7") (pin "15") (pinfunction "VSS_15") (pintype "unspecified"))
      (node (ref "U9") (pin "4") (pinfunction "GND_4") (pintype "unspecified"))
      (node (ref "XP1") (pin "6") (pinfunction "GND_6") (pintype "input"))
    )
    (net (code "111") (name "Net-(Q1-D)") (class "Default")
      (node (ref "Q1") (pin "3") (pinfunction "D_3") (pintype "unspecified"))
      (node (ref "R2") (pin "2") (pinfunction "2_2") (pintype "input"))
    )
    (net (code "112") (name "Net-(Q2-B)") (class "Default")
      (node (ref "Q2") (pin "1") (pinfunction "B_1") (pintype "input"))
      (node (ref "R8") (pin "1") (pinfunction "1_1") (pintype "input"))
    )
    (net (code "113") (name "Net-(Q2-C)") (class "Default")
      (node (ref "Q2") (pin "3") (pinfunction "C_3") (pintype "input"))
      (node (ref "R7") (pin "1") (pinfunction "1_1") (pintype "input"))
    )
    (net (code "114") (name "Net-(U9-X1)") (class "Default")
      (node (ref "U9") (pin "2") (pinfunction "X1_2") (pintype "unspecified"))
      (node (ref "X1") (pin "2") (pinfunction "OSC2_2") (pintype "input"))
    )
    (net (code "115") (name "Net-(U9-X2)") (class "Default")
      (node (ref "U9") (pin "3") (pinfunction "X2_3") (pintype "unspecified"))
      (node (ref "X1") (pin "1") (pinfunction "OSC1_1") (pintype "input"))
    )
    (net (code "116") (name "SRAM_VCC") (class "Default")
      (node (ref "C2") (pin "2") (pinfunction "2_2") (pintype "unspecified"))
      (node (ref "R1") (pin "2") (pinfunction "2_2") (pintype "input"))
      (node (ref "R9") (pin "2") (pinfunction "2_2") (pintype "input"))
      (node (ref "U3") (pin "8") (pinfunction "VDD_8") (pintype "unspecified"))
    )
    (net (code "117") (name "VMIX") (class "Default")
      (node (ref "D1") (pin "1") (pinfunction "K_1") (pintype "unspecified"))
      (node (ref "Q1") (pin "2") (pinfunction "S_2") (pintype "unspecified"))
      (node (ref "R9") (pin "1") (pinfunction "1_1") (pintype "input"))
      (node (ref "U9") (pin "8") (pinfunction "VCC1_8") (pintype "unspecified"))
    )
    (net (code "118") (name "unconnected-(U4B-IO-Pad1)") (class "Default")
      (node (ref "U4") (pin "1") (pinfunction "IO_1") (pintype "bidirectional"))
    )
    (net (code "119") (name "unconnected-(U4B-IO-Pad96)") (class "Default")
      (node (ref "U4") (pin "96") (pinfunction "IO_96") (pintype "bidirectional"))
    )
    (net (code "120") (name "unconnected-(U4B-IO-Pad97)") (class "Default")
      (node (ref "U4") (pin "97") (pinfunction "IO_97") (pintype "bidirectional"))
    )
    (net (code "121") (name "unconnected-(U4B-IO-Pad100)") (class "Default")
      (node (ref "U4") (pin "100") (pinfunction "IO_100") (pintype "bidirectional"))
    )
    (net (code "122") (name "unconnected-(U4B-IOGCLK2-Pad62)") (class "Default")
      (node (ref "U4") (pin "62") (pinfunction "IOGCLK2_62") (pintype "bidirectional"))
    )
    (net (code "123") (name "unconnected-(U4B-IOGCLK3-Pad64)") (class "Default")
      (node (ref "U4") (pin "64") (pinfunction "IOGCLK3_64") (pintype "bidirectional"))
    )
    (net (code "124") (name "unconnected-(U4E-IO-Pad2)") (class "Default")
      (node (ref "U4") (pin "2") (pinfunction "IO_2") (pintype "bidirectional"))
    )
    (net (code "125") (name "unconnected-(U4E-IO-Pad3)") (class "Default")
      (node (ref "U4") (pin "3") (pinfunction "IO_3") (pintype "bidirectional"))
    )
    (net (code "126") (name "unconnected-(U4E-IO-Pad4)") (class "Default")
      (node (ref "U4") (pin "4") (pinfunction "IO_4") (pintype "bidirectional"))
    )
    (net (code "127") (name "unconnected-(U4E-IO-Pad5)") (class "Default")
      (node (ref "U4") (pin "5") (pinfunction "IO_5") (pintype "bidirectional"))
    )
    (net (code "128") (name "unconnected-(U4E-IO-Pad6)") (class "Default")
      (node (ref "U4") (pin "6") (pinfunction "IO_6") (pintype "bidirectional"))
    )
    (net (code "129") (name "unconnected-(U4E-IO-Pad7)") (class "Default")
      (node (ref "U4") (pin "7") (pinfunction "IO_7") (pintype "bidirectional"))
    )
    (net (code "130") (name "unconnected-(U4E-IO-Pad8)") (class "Default")
      (node (ref "U4") (pin "8") (pinfunction "IO_8") (pintype "bidirectional"))
    )
    (net (code "131") (name "unconnected-(U4E-IO-Pad26)") (class "Default")
      (node (ref "U4") (pin "26") (pinfunction "IO_26") (pintype "bidirectional"))
    )
    (net (code "132") (name "unconnected-(U4E-IO-Pad33)") (class "Default")
      (node (ref "U4") (pin "33") (pinfunction "IO_33") (pintype "bidirectional"))
    )
    (net (code "133") (name "unconnected-(U4E-IODEV_CLRn-Pad44)") (class "Default")
      (node (ref "U4") (pin "44") (pinfunction "IODEV_CLRn_44") (pintype "bidirectional"))
    )
    (net (code "134") (name "unconnected-(U4E-IODEV_OE-Pad43)") (class "Default")
      (node (ref "U4") (pin "43") (pinfunction "IODEV_OE_43") (pintype "bidirectional"))
    )
    (net (code "135") (name "unconnected-(U4E-IOGCLK0-Pad12)") (class "Default")
      (node (ref "U4") (pin "12") (pinfunction "IOGCLK0_12") (pintype "bidirectional"))
    )
    (net (code "136") (name "unconnected-(U5-DQ8-Pad36)") (class "Default")
      (node (ref "U5") (pin "36") (pinfunction "DQ8_36") (pintype "unspecified"))
    )
    (net (code "137") (name "unconnected-(U5-DQ9-Pad38)") (class "Default")
      (node (ref "U5") (pin "38") (pinfunction "DQ9_38") (pintype "unspecified"))
    )
    (net (code "138") (name "unconnected-(U5-DQ10-Pad40)") (class "Default")
      (node (ref "U5") (pin "40") (pinfunction "DQ10_40") (pintype "unspecified"))
    )
    (net (code "139") (name "unconnected-(U5-DQ11-Pad42)") (class "Default")
      (node (ref "U5") (pin "42") (pinfunction "DQ11_42") (pintype "unspecified"))
    )
    (net (code "140") (name "unconnected-(U5-DQ12-Pad45)") (class "Default")
      (node (ref "U5") (pin "45") (pinfunction "DQ12_45") (pintype "unspecified"))
    )
    (net (code "141") (name "unconnected-(U5-DQ13-Pad47)") (class "Default")
      (node (ref "U5") (pin "47") (pinfunction "DQ13_47") (pintype "unspecified"))
    )
    (net (code "142") (name "unconnected-(U5-DQ14-Pad49)") (class "Default")
      (node (ref "U5") (pin "49") (pinfunction "DQ14_49") (pintype "unspecified"))
    )
    (net (code "143") (name "unconnected-(U5-NC-Pad27)") (class "Default")
      (node (ref "U5") (pin "27") (pinfunction "NC_27") (pintype "unspecified"))
    )
    (net (code "144") (name "unconnected-(U5-NC-Pad28)") (class "Default")
      (node (ref "U5") (pin "28") (pinfunction "NC_28") (pintype "unspecified"))
    )
    (net (code "145") (name "unconnected-(U5-NC-Pad30)") (class "Default")
      (node (ref "U5") (pin "30") (pinfunction "NC_30") (pintype "unspecified"))
    )
    (net (code "146") (name "unconnected-(U5-NC-Pad55)") (class "Default")
      (node (ref "U5") (pin "55") (pinfunction "NC_55") (pintype "unspecified"))
    )
    (net (code "147") (name "unconnected-(U5-NC-Pad56)") (class "Default")
      (node (ref "U5") (pin "56") (pinfunction "NC_56") (pintype "unspecified"))
    )
    (net (code "148") (name "unconnected-(U5-RY{slash}BY#-Pad17)") (class "Default")
      (node (ref "U5") (pin "17") (pinfunction "RY/BY#_17") (pintype "unspecified"))
    )
    (net (code "149") (name "unconnected-(U5-WP#{slash}ACC-Pad16)") (class "Default")
      (node (ref "U5") (pin "16") (pinfunction "WP#/ACC_16") (pintype "unspecified"))
    )
  )
)
